# SSOP-28_v10.net
KiCad netlist of a schematic drawn in EAGLE
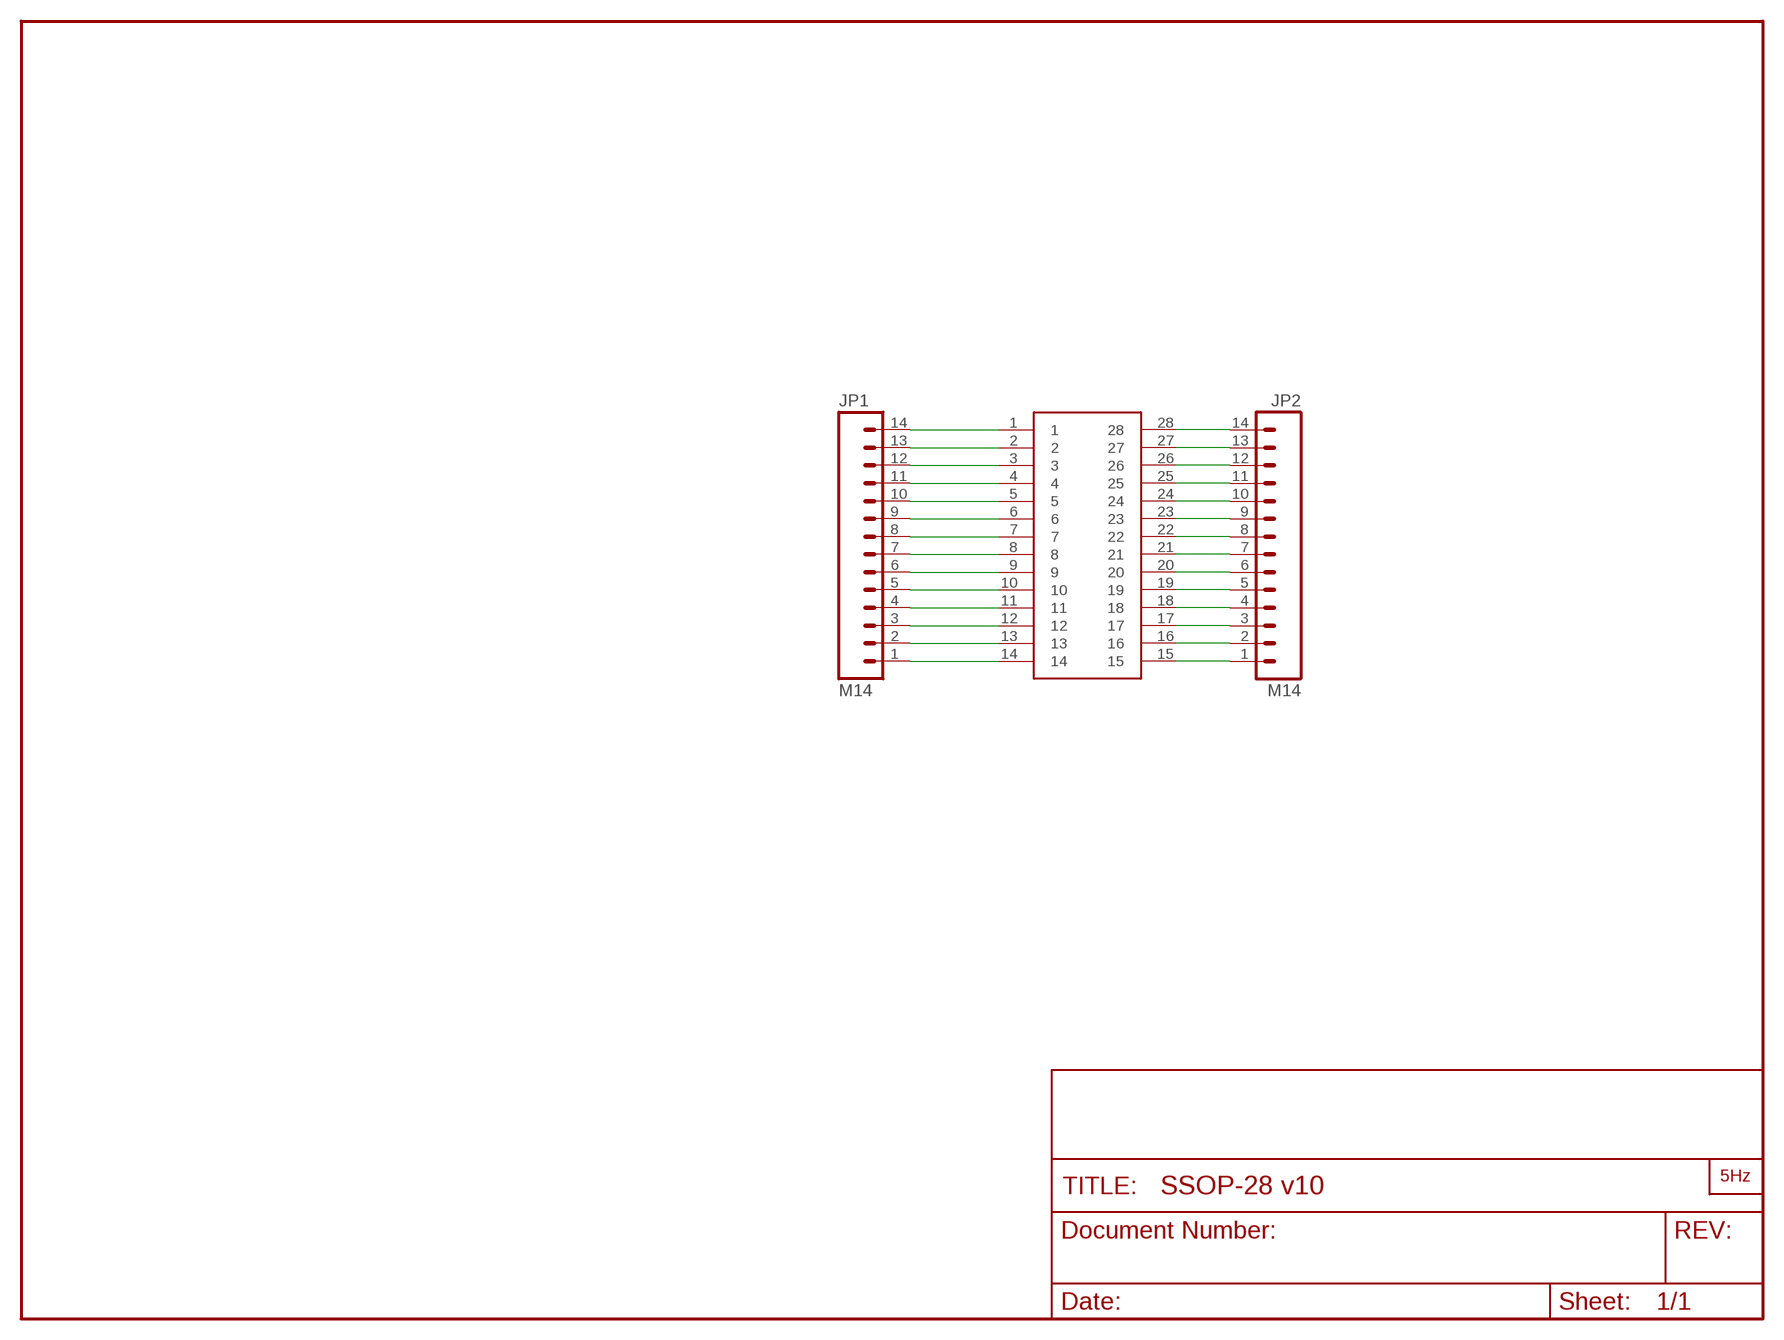
[diagram p0: schematic, sheet 1]

(export (version "E")
  (design (tool "Eeschema 10.0.6"))
  (components
    (comp (ref "JP1")
      (value "M14")
      (footprint "eagle-import:1X14")
      (libsource (lib "eagle-import") (part "M14"))
    )
    (comp (ref "JP2")
      (value "M14")
      (footprint "eagle-import:1X14")
      (libsource (lib "eagle-import") (part "M14"))
    )
    (comp (ref "U$1")
      (value "SSOP28")
      (footprint "eagle-import:SSOP28DB")
      (libsource (lib "eagle-import") (part "SSOP28"))
    )
    (comp (ref "U$2")
      (value "LOGO2_SILK10MM")
      (footprint "eagle-import:LOGO2_10MM")
      (libsource (lib "eagle-import") (part "LOGO2_SILK10MM"))
    )
  )
  (nets
    (net (code "1") (name "Net-(JP1-Pad1)") (class "Default")
      (node (ref "JP1") (pin "1") (pinfunction "1_1") (pintype "passive"))
      (node (ref "U$1") (pin "14") (pinfunction "14_14") (pintype "bidirectional"))
    )
    (net (code "2") (name "Net-(JP1-Pad2)") (class "Default")
      (node (ref "JP1") (pin "2") (pinfunction "2_2") (pintype "passive"))
      (node (ref "U$1") (pin "13") (pinfunction "13_13") (pintype "bidirectional"))
    )
    (net (code "3") (name "Net-(JP1-Pad3)") (class "Default")
      (node (ref "JP1") (pin "3") (pinfunction "3_3") (pintype "passive"))
      (node (ref "U$1") (pin "12") (pinfunction "12_12") (pintype "bidirectional"))
    )
    (net (code "4") (name "Net-(JP1-Pad4)") (class "Default")
      (node (ref "JP1") (pin "4") (pinfunction "4_4") (pintype "passive"))
      (node (ref "U$1") (pin "11") (pinfunction "11_11") (pintype "bidirectional"))
    )
    (net (code "5") (name "Net-(JP1-Pad5)") (class "Default")
      (node (ref "JP1") (pin "5") (pinfunction "5_5") (pintype "passive"))
      (node (ref "U$1") (pin "10") (pinfunction "10_10") (pintype "bidirectional"))
    )
    (net (code "6") (name "Net-(JP1-Pad6)") (class "Default")
      (node (ref "JP1") (pin "6") (pinfunction "6_6") (pintype "passive"))
      (node (ref "U$1") (pin "9") (pinfunction "9_9") (pintype "bidirectional"))
    )
    (net (code "7") (name "Net-(JP1-Pad7)") (class "Default")
      (node (ref "JP1") (pin "7") (pinfunction "7_7") (pintype "passive"))
      (node (ref "U$1") (pin "8") (pinfunction "8_8") (pintype "bidirectional"))
    )
    (net (code "8") (name "Net-(JP1-Pad8)") (class "Default")
      (node (ref "JP1") (pin "8") (pinfunction "8_8") (pintype "passive"))
      (node (ref "U$1") (pin "7") (pinfunction "7_7") (pintype "bidirectional"))
    )
    (net (code "9") (name "Net-(JP1-Pad9)") (class "Default")
      (node (ref "JP1") (pin "9") (pinfunction "9_9") (pintype "passive"))
      (node (ref "U$1") (pin "6") (pinfunction "6_6") (pintype "bidirectional"))
    )
    (net (code "10") (name "Net-(JP1-Pad10)") (class "Default")
      (node (ref "JP1") (pin "10") (pinfunction "10_10") (pintype "passive"))
      (node (ref "U$1") (pin "5") (pinfunction "5_5") (pintype "bidirectional"))
    )
    (net (code "11") (name "Net-(JP1-Pad11)") (class "Default")
      (node (ref "JP1") (pin "11") (pinfunction "11_11") (pintype "passive"))
      (node (ref "U$1") (pin "4") (pinfunction "4_4") (pintype "bidirectional"))
    )
    (net (code "12") (name "Net-(JP1-Pad12)") (class "Default")
      (node (ref "JP1") (pin "12") (pinfunction "12_12") (pintype "passive"))
      (node (ref "U$1") (pin "3") (pinfunction "3_3") (pintype "bidirectional"))
    )
    (net (code "13") (name "Net-(JP1-Pad13)") (class "Default")
      (node (ref "JP1") (pin "13") (pinfunction "13_13") (pintype "passive"))
      (node (ref "U$1") (pin "2") (pinfunction "2_2") (pintype "bidirectional"))
    )
    (net (code "14") (name "Net-(JP1-Pad14)") (class "Default")
      (node (ref "JP1") (pin "14") (pinfunction "14_14") (pintype "passive"))
      (node (ref "U$1") (pin "1") (pinfunction "1_1") (pintype "bidirectional"))
    )
    (net (code "15") (name "Net-(JP2-Pad1)") (class "Default")
      (node (ref "JP2") (pin "1") (pinfunction "1_1") (pintype "passive"))
      (node (ref "U$1") (pin "15") (pinfunction "15_15") (pintype "bidirectional"))
    )
    (net (code "16") (name "Net-(JP2-Pad2)") (class "Default")
      (node (ref "JP2") (pin "2") (pinfunction "2_2") (pintype "passive"))
      (node (ref "U$1") (pin "16") (pinfunction "16_16") (pintype "bidirectional"))
    )
    (net (code "17") (name "Net-(JP2-Pad3)") (class "Default")
      (node (ref "JP2") (pin "3") (pinfunction "3_3") (pintype "passive"))
      (node (ref "U$1") (pin "17") (pinfunction "17_17") (pintype "bidirectional"))
    )
    (net (code "18") (name "Net-(JP2-Pad4)") (class "Default")
      (node (ref "JP2") (pin "4") (pinfunction "4_4") (pintype "passive"))
      (node (ref "U$1") (pin "18") (pinfunction "18_18") (pintype "bidirectional"))
    )
    (net (code "19") (name "Net-(JP2-Pad5)") (class "Default")
      (node (ref "JP2") (pin "5") (pinfunction "5_5") (pintype "passive"))
      (node (ref "U$1") (pin "19") (pinfunction "19_19") (pintype "bidirectional"))
    )
    (net (code "20") (name "Net-(JP2-Pad6)") (class "Default")
      (node (ref "JP2") (pin "6") (pinfunction "6_6") (pintype "passive"))
      (node (ref "U$1") (pin "20") (pinfunction "20_20") (pintype "bidirectional"))
    )
    (net (code "21") (name "Net-(JP2-Pad7)") (class "Default")
      (node (ref "JP2") (pin "7") (pinfunction "7_7") (pintype "passive"))
      (node (ref "U$1") (pin "21") (pinfunction "21_21") (pintype "bidirectional"))
    )
    (net (code "22") (name "Net-(JP2-Pad8)") (class "Default")
      (node (ref "JP2") (pin "8") (pinfunction "8_8") (pintype "passive"))
      (node (ref "U$1") (pin "22") (pinfunction "22_22") (pintype "bidirectional"))
    )
    (net (code "23") (name "Net-(JP2-Pad9)") (class "Default")
      (node (ref "JP2") (pin "9") (pinfunction "9_9") (pintype "passive"))
      (node (ref "U$1") (pin "23") (pinfunction "23_23") (pintype "bidirectional"))
    )
    (net (code "24") (name "Net-(JP2-Pad10)") (class "Default")
      (node (ref "JP2") (pin "10") (pinfunction "10_10") (pintype "passive"))
      (node (ref "U$1") (pin "24") (pinfunction "24_24") (pintype "bidirectional"))
    )
    (net (code "25") (name "Net-(JP2-Pad11)") (class "Default")
      (node (ref "JP2") (pin "11") (pinfunction "11_11") (pintype "passive"))
      (node (ref "U$1") (pin "25") (pinfunction "25_25") (pintype "bidirectional"))
    )
    (net (code "26") (name "Net-(JP2-Pad12)") (class "Default")
      (node (ref "JP2") (pin "12") (pinfunction "12_12") (pintype "passive"))
      (node (ref "U$1") (pin "26") (pinfunction "26_26") (pintype "bidirectional"))
    )
    (net (code "27") (name "Net-(JP2-Pad13)") (class "Default")
      (node (ref "JP2") (pin "13") (pinfunction "13_13") (pintype "passive"))
      (node (ref "U$1") (pin "27") (pinfunction "27_27") (pintype "bidirectional"))
    )
    (net (code "28") (name "Net-(JP2-Pad14)") (class "Default")
      (node (ref "JP2") (pin "14") (pinfunction "14_14") (pintype "passive"))
      (node (ref "U$1") (pin "28") (pinfunction "28_28") (pintype "bidirectional"))
    )
  )
)
